# ATmega1284p_breakout.net
KiCad netlist of a schematic drawn in Altium Designer
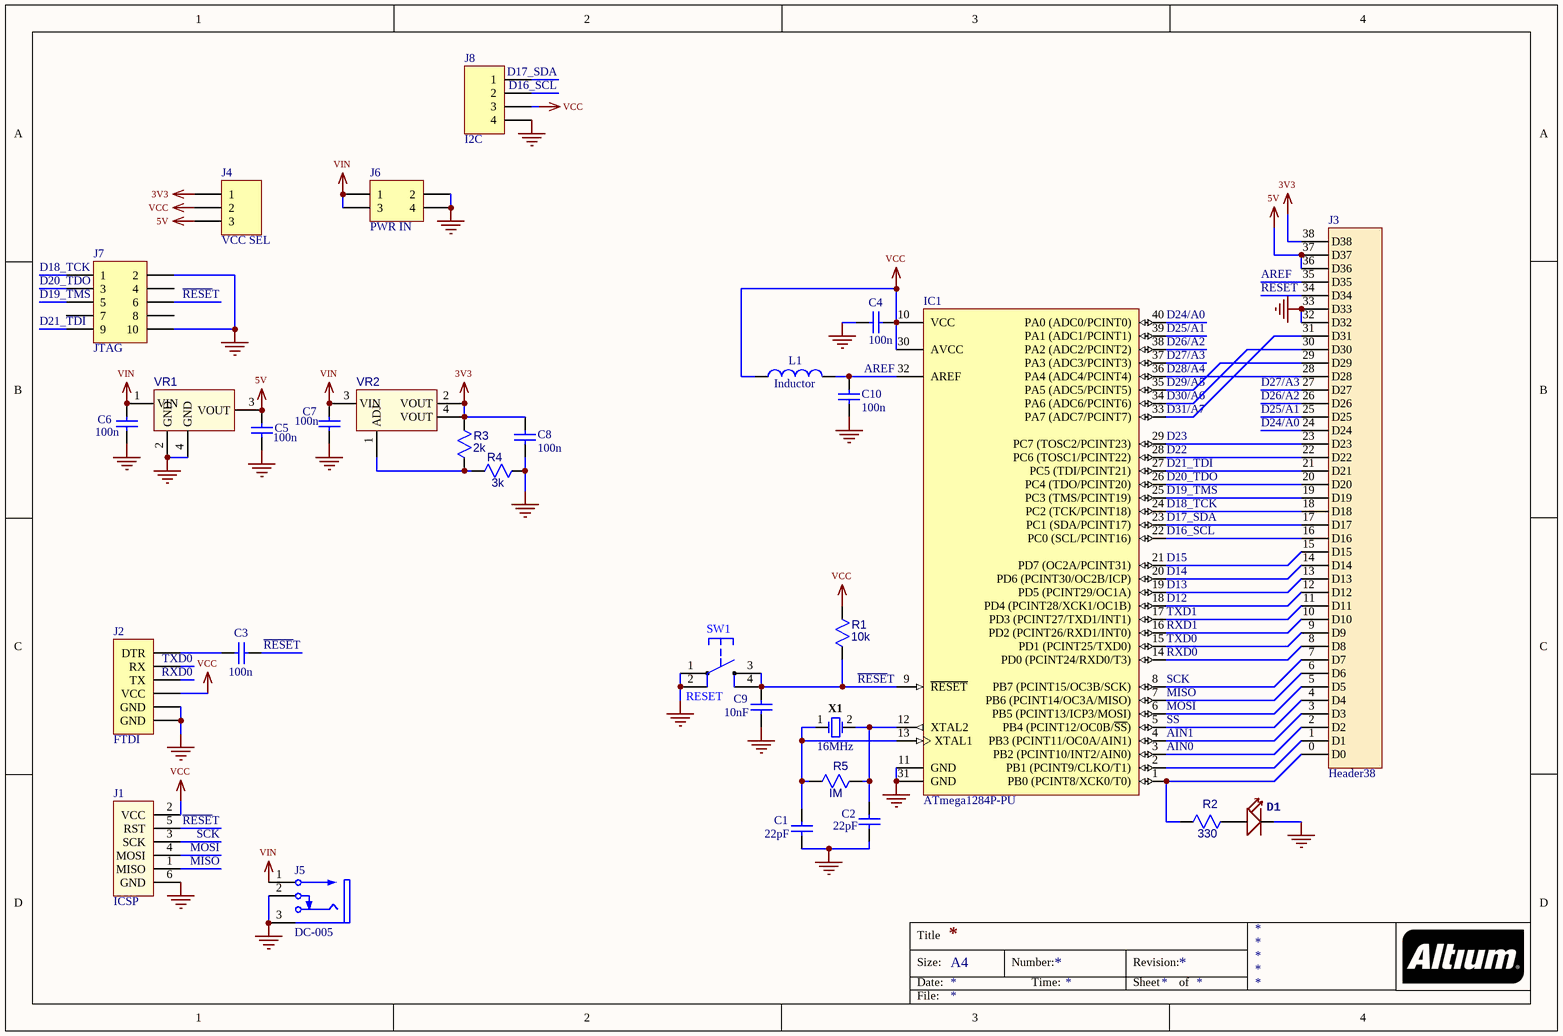
[diagram p0: ATmega1284p_breakout.SchDoc]

(export (version "E")
  (design (tool "Eeschema 10.0.6"))
  (components
    (comp (ref "C1")
      (value "22pF")
      (footprint "RESC0805(2012)_M:RESC0805(2012)_M")
      (description "Capacitor (Semiconductor SIM Model)")
      (fields (field (name "Comment") "Cap Semi"))
      (libsource (lib "Miscellaneous Devices") (part "Cap Semi"))
    )
    (comp (ref "C2")
      (value "22pF")
      (footprint "RESC0805(2012)_M:RESC0805(2012)_M")
      (description "Capacitor (Semiconductor SIM Model)")
      (fields (field (name "Comment") "Cap Semi"))
      (libsource (lib "Miscellaneous Devices") (part "Cap Semi"))
    )
    (comp (ref "C3")
      (value "100n")
      (footprint "RESC0805(2012)_M:RESC0805(2012)_M")
      (description "Capacitor (Semiconductor SIM Model)")
      (fields (field (name "Comment") "Cap Semi"))
      (libsource (lib "Miscellaneous Devices") (part "Cap Semi"))
    )
    (comp (ref "C4")
      (value "100n")
      (footprint "RESC0805(2012)_M:RESC0805(2012)_M")
      (description "Capacitor (Semiconductor SIM Model)")
      (fields (field (name "Comment") "Cap Semi"))
      (libsource (lib "Miscellaneous Devices") (part "Cap Semi"))
    )
    (comp (ref "C5")
      (value "100n")
      (footprint "RESC0805(2012)_M:RESC0805(2012)_M")
      (description "Capacitor (Semiconductor SIM Model)")
      (fields (field (name "Comment") "Cap Semi"))
      (libsource (lib "Miscellaneous Devices") (part "Cap Semi"))
    )
    (comp (ref "C6")
      (value "100n")
      (footprint "RESC0805(2012)_M:RESC0805(2012)_M")
      (description "Capacitor (Semiconductor SIM Model)")
      (fields (field (name "Comment") "Cap Semi"))
      (libsource (lib "Miscellaneous Devices") (part "Cap Semi"))
    )
    (comp (ref "C7")
      (value "100n")
      (footprint "RESC0805(2012)_M:RESC0805(2012)_M")
      (description "Capacitor (Semiconductor SIM Model)")
      (fields (field (name "Comment") "Cap Semi"))
      (libsource (lib "Miscellaneous Devices") (part "Cap Semi"))
    )
    (comp (ref "C8")
      (value "100n")
      (footprint "RESC0805(2012)_M:RESC0805(2012)_M")
      (description "Capacitor (Semiconductor SIM Model)")
      (fields (field (name "Comment") "Cap Semi"))
      (libsource (lib "Miscellaneous Devices") (part "Cap Semi"))
    )
    (comp (ref "C9")
      (value "10nF")
      (footprint "RESC0805(2012)_M:RESC0805(2012)_M")
      (description "Capacitor (Semiconductor SIM Model)")
      (fields (field (name "Comment") "Cap Semi"))
      (libsource (lib "Miscellaneous Devices") (part "Cap Semi"))
    )
    (comp (ref "C10")
      (value "100n")
      (footprint "RESC0805(2012)_M:RESC0805(2012)_M")
      (description "Capacitor (Semiconductor SIM Model)")
      (fields (field (name "Comment") "Cap Semi"))
      (libsource (lib "Miscellaneous Devices") (part "Cap Semi"))
    )
    (comp (ref "D1")
      (value "LED")
      (footprint "LED-0805")
      (fields (field (name "MPN") "17-215SURC/S530-A2/TR8"))
      (libsource (lib "105848_revD3") (part "SMD-LED-CLEAR-RED(0805)"))
    )
    (comp (ref "IC1")
      (value "ATmega1284P-PU")
      (footprint "40P6")
      (libsource (lib "Atmel Microcontroller megaAVR") (part "ATmega1284P-PU"))
    )
    (comp (ref "J1")
      (value "ICSP")
      (footprint "ICSP")
      (description "In-Circuit Serial Programming Header")
      (libsource (lib "AltiumIntegratedLibrary") (part "ICSP"))
    )
    (comp (ref "J2")
      (value "FTDI")
      (footprint "HDR1X6")
      (description "Header, 6-Pin")
      (fields (field (name "PUBLISHER") "Altium Limited"))
      (libsource (lib "Miscellaneous Connectors") (part "MHDR1X6"))
    )
    (comp (ref "J3")
      (value "Header38")
      (footprint "Header38")
      (libsource (lib "ATmega1284p_breakout") (part "Component_1"))
    )
    (comp (ref "J4")
      (value "VCC SEL")
      (footprint "HDR1X3")
      (description "Header, 3-Pin")
      (fields (field (name "PUBLISHER") "Altium Limited"))
      (libsource (lib "Miscellaneous Connectors") (part "Header 3"))
    )
    (comp (ref "J5")
      (value "DC-005")
      (footprint "DCJ3P-14.2X11.0X9.0MM")
      (libsource (lib "ATmega1284p_breakout") (part "DC BARREL"))
    )
    (comp (ref "J6")
      (value "PWR IN")
      (footprint "HDR2X2")
      (description "Header, 2-Pin, Dual row")
      (fields (field (name "PUBLISHER") "Altium Limited"))
      (libsource (lib "Miscellaneous Connectors") (part "Header 2X2"))
    )
    (comp (ref "J7")
      (value "JTAG")
      (footprint "HDR2X5")
      (description "Header, 5-Pin, Dual row")
      (fields (field (name "PUBLISHER") "Altium Limited"))
      (libsource (lib "Miscellaneous Connectors") (part "Header 5X2"))
    )
    (comp (ref "J8")
      (value "I2C")
      (footprint "HDR1X4")
      (description "Header, 4-Pin")
      (fields (field (name "PUBLISHER") "Altium Limited"))
      (libsource (lib "Miscellaneous Connectors") (part "Header 4"))
    )
    (comp (ref "L1")
      (value "Inductor")
      (footprint "2029")
      (fields (field (name "PUBLISHER") "Altium Limited"))
      (libsource (lib "Miscellaneous Devices") (part "Inductor"))
    )
    (comp (ref "R1")
      (value "10k")
      (footprint "CAPC0805(2012)75_N")
      (description "RES_0805")
      (libsource (lib "AltiumIntegratedLibrary") (part "RES_0805"))
    )
    (comp (ref "R2")
      (value "330")
      (footprint "CAPC0805(2012)75_N")
      (description "RES_0805")
      (libsource (lib "AltiumIntegratedLibrary") (part "RES_0805"))
    )
    (comp (ref "R3")
      (value "2k")
      (footprint "CAPC0805(2012)75_N")
      (description "RES_0805")
      (libsource (lib "AltiumIntegratedLibrary") (part "RES_0805"))
    )
    (comp (ref "R4")
      (value "3k")
      (footprint "CAPC0805(2012)75_N")
      (description "RES_0805")
      (libsource (lib "AltiumIntegratedLibrary") (part "RES_0805"))
    )
    (comp (ref "R5")
      (value "IM")
      (footprint "CAPC0805(2012)75_N")
      (description "RES_0805")
      (libsource (lib "AltiumIntegratedLibrary") (part "RES_0805"))
    )
    (comp (ref "SW1")
      (value "RESET")
      (footprint "TACT_SW")
      (libsource (lib "AltiumIntegratedLibrary") (part "TACT_SW"))
    )
    (comp (ref "VR1")
      (value "LDL1117S50R")
      (footprint "SOT223_M")
      (description "Fixed 5V Voltage Regulator")
      (fields (field (name "MFR") "TI") (field (name "MPN") "LM340MP-5.0"))
      (libsource (lib "105848_revD3") (part "LM317"))
    )
    (comp (ref "VR2")
      (value "LM117")
      (footprint "SOT223_M")
      (description "Adjustable Voltage Regulator")
      (fields (field (name "MFR") "TI") (field (name "MPN") "LM340MP-5.0"))
      (libsource (lib "") (part "LM317_1"))
    )
    (comp (ref "X1")
      (value "16MHz")
      (footprint "Crystal")
      (libsource (lib "ATmega1284p_breakout") (part "XTAL-HC"))
    )
  )
  (nets
    (net (code "1") (name "/AIN0") (class "Default")
      (node (ref "IC1") (pin "3") (pinfunction "PB2_(PCINT10/INT2/AIN0)_3") (pintype "bidirectional"))
      (node (ref "J3") (pin "2") (pinfunction "D2_2") (pintype "passive"))
    )
    (net (code "2") (name "/AIN1") (class "Default")
      (node (ref "IC1") (pin "4") (pinfunction "PB3_(PCINT11/OC0A/AIN1)_4") (pintype "bidirectional"))
      (node (ref "J3") (pin "3") (pinfunction "D3_3") (pintype "passive"))
    )
    (net (code "3") (name "/AREF") (class "Default")
      (node (ref "C10") (pin "2") (pinfunction "2_2") (pintype "passive"))
      (node (ref "IC1") (pin "32") (pinfunction "AREF_32") (pintype "power_in"))
      (node (ref "J3") (pin "35") (pinfunction "D35_35") (pintype "passive"))
      (node (ref "L1") (pin "2") (pinfunction "2_2") (pintype "passive"))
    )
    (net (code "4") (name "/D12") (class "Default")
      (node (ref "IC1") (pin "18") (pinfunction "PD4_(PCINT28/XCK1/OC1B)_18") (pintype "bidirectional"))
      (node (ref "J3") (pin "12") (pinfunction "D12_12") (pintype "passive"))
    )
    (net (code "5") (name "/D13") (class "Default")
      (node (ref "IC1") (pin "19") (pinfunction "PD5_(PCINT29/OC1A)_19") (pintype "bidirectional"))
      (node (ref "J3") (pin "13") (pinfunction "D13_13") (pintype "passive"))
    )
    (net (code "6") (name "/D14") (class "Default")
      (node (ref "IC1") (pin "20") (pinfunction "PD6_(PCINT30/OC2B/ICP)_20") (pintype "bidirectional"))
      (node (ref "J3") (pin "14") (pinfunction "D14_14") (pintype "passive"))
    )
    (net (code "7") (name "/D15") (class "Default")
      (node (ref "IC1") (pin "21") (pinfunction "PD7_(OC2A/PCINT31)_21") (pintype "bidirectional"))
      (node (ref "J3") (pin "15") (pinfunction "D15_15") (pintype "passive"))
    )
    (net (code "8") (name "/D16_SCL") (class "Default")
      (node (ref "IC1") (pin "22") (pinfunction "PC0_(SCL/PCINT16)_22") (pintype "bidirectional"))
      (node (ref "J3") (pin "16") (pinfunction "D16_16") (pintype "passive"))
      (node (ref "J8") (pin "2") (pinfunction "2_2") (pintype "passive"))
    )
    (net (code "9") (name "/D17_SDA") (class "Default")
      (node (ref "IC1") (pin "23") (pinfunction "PC1_(SDA/PCINT17)_23") (pintype "bidirectional"))
      (node (ref "J3") (pin "17") (pinfunction "D17_17") (pintype "passive"))
      (node (ref "J8") (pin "1") (pinfunction "1_1") (pintype "passive"))
    )
    (net (code "10") (name "/D18_TCK") (class "Default")
      (node (ref "IC1") (pin "24") (pinfunction "PC2_(TCK/PCINT18)_24") (pintype "bidirectional"))
      (node (ref "J3") (pin "18") (pinfunction "D18_18") (pintype "passive"))
      (node (ref "J7") (pin "1") (pinfunction "1_1") (pintype "passive"))
    )
    (net (code "11") (name "/D19_TMS") (class "Default")
      (node (ref "IC1") (pin "25") (pinfunction "PC3_(TMS/PCINT19)_25") (pintype "bidirectional"))
      (node (ref "J3") (pin "19") (pinfunction "D19_19") (pintype "passive"))
      (node (ref "J7") (pin "5") (pinfunction "5_5") (pintype "passive"))
    )
    (net (code "12") (name "/D20_TDO") (class "Default")
      (node (ref "IC1") (pin "26") (pinfunction "PC4_(TDO/PCINT20)_26") (pintype "bidirectional"))
      (node (ref "J3") (pin "20") (pinfunction "D20_20") (pintype "passive"))
      (node (ref "J7") (pin "3") (pinfunction "3_3") (pintype "passive"))
    )
    (net (code "13") (name "/D21_TDI") (class "Default")
      (node (ref "IC1") (pin "27") (pinfunction "PC5_(TDI/PCINT21)_27") (pintype "bidirectional"))
      (node (ref "J3") (pin "21") (pinfunction "D21_21") (pintype "passive"))
      (node (ref "J7") (pin "9") (pinfunction "9_9") (pintype "passive"))
    )
    (net (code "14") (name "/D22") (class "Default")
      (node (ref "IC1") (pin "28") (pinfunction "PC6_(TOSC1/PCINT22)_28") (pintype "bidirectional"))
      (node (ref "J3") (pin "22") (pinfunction "D22_22") (pintype "passive"))
    )
    (net (code "15") (name "/D23") (class "Default")
      (node (ref "IC1") (pin "29") (pinfunction "PC7_(TOSC2/PCINT23)_29") (pintype "bidirectional"))
      (node (ref "J3") (pin "23") (pinfunction "D23_23") (pintype "passive"))
    )
    (net (code "16") (name "/D24{slash}A0") (class "Default")
      (node (ref "IC1") (pin "40") (pinfunction "PA0_(ADC0/PCINT0)_40") (pintype "bidirectional"))
      (node (ref "J3") (pin "24") (pinfunction "D24_24") (pintype "passive"))
    )
    (net (code "17") (name "/D25{slash}A1") (class "Default")
      (node (ref "IC1") (pin "39") (pinfunction "PA1_(ADC1/PCINT1)_39") (pintype "bidirectional"))
      (node (ref "J3") (pin "25") (pinfunction "D25_25") (pintype "passive"))
    )
    (net (code "18") (name "/D26{slash}A2") (class "Default")
      (node (ref "IC1") (pin "38") (pinfunction "PA2_(ADC2/PCINT2)_38") (pintype "bidirectional"))
      (node (ref "J3") (pin "26") (pinfunction "D26_26") (pintype "passive"))
    )
    (net (code "19") (name "/D27{slash}A3") (class "Default")
      (node (ref "IC1") (pin "37") (pinfunction "PA3_(ADC3/PCINT3)_37") (pintype "bidirectional"))
      (node (ref "J3") (pin "27") (pinfunction "D27_27") (pintype "passive"))
    )
    (net (code "20") (name "/D28{slash}A4") (class "Default")
      (node (ref "IC1") (pin "36") (pinfunction "PA4_(ADC4/PCINT4)_36") (pintype "bidirectional"))
      (node (ref "J3") (pin "28") (pinfunction "D28_28") (pintype "passive"))
    )
    (net (code "21") (name "/D29{slash}A5") (class "Default")
      (node (ref "IC1") (pin "35") (pinfunction "PA5_(ADC5/PCINT5)_35") (pintype "bidirectional"))
      (node (ref "J3") (pin "29") (pinfunction "D29_29") (pintype "passive"))
    )
    (net (code "22") (name "/D30{slash}A6") (class "Default")
      (node (ref "IC1") (pin "34") (pinfunction "PA6_(ADC6/PCINT6)_34") (pintype "bidirectional"))
      (node (ref "J3") (pin "30") (pinfunction "D30_30") (pintype "passive"))
    )
    (net (code "23") (name "/D31{slash}A7") (class "Default")
      (node (ref "IC1") (pin "33") (pinfunction "PA7_(ADC7/PCINT7)_33") (pintype "bidirectional"))
      (node (ref "J3") (pin "31") (pinfunction "D31_31") (pintype "passive"))
    )
    (net (code "24") (name "/MISO") (class "Default")
      (node (ref "IC1") (pin "7") (pinfunction "PB6_(PCINT14/OC3A/MISO)_7") (pintype "bidirectional"))
      (node (ref "J1") (pin "1") (pinfunction "MISO_1") (pintype "passive"))
      (node (ref "J3") (pin "6") (pinfunction "D6_6") (pintype "passive"))
    )
    (net (code "25") (name "/MOSI") (class "Default")
      (node (ref "IC1") (pin "6") (pinfunction "PB5_(PCINT13/ICP3/MOSI)_6") (pintype "bidirectional"))
      (node (ref "J1") (pin "4") (pinfunction "MOSI_4") (pintype "passive"))
      (node (ref "J3") (pin "5") (pinfunction "D5_5") (pintype "passive"))
    )
    (net (code "26") (name "/RXD0") (class "Default")
      (node (ref "IC1") (pin "14") (pinfunction "PD0_(PCINT24/RXD0/T3)_14") (pintype "bidirectional"))
      (node (ref "J2") (pin "3") (pinfunction "TX_3") (pintype "passive"))
      (node (ref "J3") (pin "8") (pinfunction "D8_8") (pintype "passive"))
    )
    (net (code "27") (name "/RXD1") (class "Default")
      (node (ref "IC1") (pin "16") (pinfunction "PD2_(PCINT26/RXD1/INT0)_16") (pintype "bidirectional"))
      (node (ref "J3") (pin "10") (pinfunction "D10_10") (pintype "passive"))
    )
    (net (code "28") (name "/SCK") (class "Default")
      (node (ref "IC1") (pin "8") (pinfunction "PB7_(PCINT15/OC3B/SCK)_8") (pintype "bidirectional"))
      (node (ref "J1") (pin "3") (pinfunction "SCK_3") (pintype "passive"))
      (node (ref "J3") (pin "7") (pinfunction "D7_7") (pintype "passive"))
    )
    (net (code "29") (name "/TXD0") (class "Default")
      (node (ref "IC1") (pin "15") (pinfunction "PD1_(PCINT25/TXD0)_15") (pintype "bidirectional"))
      (node (ref "J2") (pin "2") (pinfunction "RX_2") (pintype "passive"))
      (node (ref "J3") (pin "9") (pinfunction "D9_9") (pintype "passive"))
    )
    (net (code "30") (name "/TXD1") (class "Default")
      (node (ref "IC1") (pin "17") (pinfunction "PD3_(PCINT27/TXD1/INT1)_17") (pintype "bidirectional"))
      (node (ref "J3") (pin "11") (pinfunction "D11_11") (pintype "passive"))
    )
    (net (code "31") (name "/~{RESE}T") (class "Default")
      (node (ref "C3") (pin "2") (pinfunction "2_2") (pintype "passive"))
      (node (ref "C9") (pin "2") (pinfunction "2_2") (pintype "passive"))
      (node (ref "IC1") (pin "9") (pinfunction "~{RESET}_9") (pintype "input"))
      (node (ref "J1") (pin "5") (pinfunction "RST_5") (pintype "passive"))
      (node (ref "J3") (pin "34") (pinfunction "D34_34") (pintype "passive"))
      (node (ref "J7") (pin "6") (pinfunction "6_6") (pintype "passive"))
      (node (ref "R1") (pin "1") (pintype "passive"))
      (node (ref "SW1") (pin "3") (pinfunction "3_3") (pintype "passive"))
      (node (ref "SW1") (pin "4") (pinfunction "4_4") (pintype "passive"))
    )
    (net (code "32") (name "/~{S}S") (class "Default")
      (node (ref "IC1") (pin "5") (pinfunction "PB4_(PCINT12/OC0B/~{SS})_5") (pintype "bidirectional"))
      (node (ref "J3") (pin "4") (pinfunction "D4_4") (pintype "passive"))
    )
    (net (code "33") (name "3V3") (class "Default")
      (node (ref "C8") (pin "2") (pinfunction "2_2") (pintype "passive"))
      (node (ref "J3") (pin "38") (pinfunction "D38_38") (pintype "passive"))
      (node (ref "J4") (pin "1") (pinfunction "1_1") (pintype "passive"))
      (node (ref "R3") (pin "2") (pintype "passive"))
      (node (ref "VR2") (pin "2") (pinfunction "VOUT_2") (pintype "passive"))
      (node (ref "VR2") (pin "4") (pinfunction "VOUT_4") (pintype "passive"))
    )
    (net (code "34") (name "5V") (class "Default")
      (node (ref "C5") (pin "2") (pinfunction "2_2") (pintype "passive"))
      (node (ref "J3") (pin "36") (pinfunction "D36_36") (pintype "passive"))
      (node (ref "J3") (pin "37") (pinfunction "D37_37") (pintype "passive"))
      (node (ref "J4") (pin "3") (pinfunction "3_3") (pintype "passive"))
      (node (ref "VR1") (pin "3") (pinfunction "VOUT_3") (pintype "passive"))
    )
    (net (code "35") (name "GND") (class "Default")
      (node (ref "C1") (pin "1") (pinfunction "1_1") (pintype "passive"))
      (node (ref "C10") (pin "1") (pinfunction "1_1") (pintype "passive"))
      (node (ref "C2") (pin "1") (pinfunction "1_1") (pintype "passive"))
      (node (ref "C4") (pin "1") (pinfunction "1_1") (pintype "passive"))
      (node (ref "C5") (pin "1") (pinfunction "1_1") (pintype "passive"))
      (node (ref "C6") (pin "1") (pinfunction "1_1") (pintype "passive"))
      (node (ref "C7") (pin "1") (pinfunction "1_1") (pintype "passive"))
      (node (ref "C8") (pin "1") (pinfunction "1_1") (pintype "passive"))
      (node (ref "C9") (pin "1") (pinfunction "1_1") (pintype "passive"))
      (node (ref "D1") (pin "-") (pinfunction "-_-") (pintype "passive"))
      (node (ref "IC1") (pin "11") (pinfunction "GND_11") (pintype "power_in"))
      (node (ref "IC1") (pin "31") (pinfunction "GND_31") (pintype "power_in"))
      (node (ref "J1") (pin "6") (pinfunction "GND_6") (pintype "passive"))
      (node (ref "J2") (pin "5") (pinfunction "GND_5") (pintype "passive"))
      (node (ref "J2") (pin "6") (pinfunction "GND_6") (pintype "passive"))
      (node (ref "J3") (pin "32") (pinfunction "D32_32") (pintype "passive"))
      (node (ref "J3") (pin "33") (pinfunction "D33_33") (pintype "passive"))
      (node (ref "J5") (pin "2") (pinfunction "2_2") (pintype "passive"))
      (node (ref "J5") (pin "3") (pinfunction "3_3") (pintype "passive"))
      (node (ref "J6") (pin "2") (pinfunction "2_2") (pintype "passive"))
      (node (ref "J6") (pin "4") (pinfunction "4_4") (pintype "passive"))
      (node (ref "J7") (pin "10") (pinfunction "10_10") (pintype "passive"))
      (node (ref "J7") (pin "2") (pinfunction "2_2") (pintype "passive"))
      (node (ref "J8") (pin "4") (pinfunction "4_4") (pintype "passive"))
      (node (ref "R4") (pin "1") (pintype "passive"))
      (node (ref "SW1") (pin "1") (pinfunction "1_1") (pintype "passive"))
      (node (ref "SW1") (pin "2") (pinfunction "2_2") (pintype "passive"))
      (node (ref "VR1") (pin "2") (pinfunction "GND_2") (pintype "power_in"))
      (node (ref "VR1") (pin "4") (pinfunction "GND_4") (pintype "passive"))
    )
    (net (code "36") (name "Net-(D1-Pad+)") (class "Default")
      (node (ref "D1") (pin "+") (pinfunction "+_+") (pintype "passive"))
      (node (ref "R2") (pin "1") (pintype "passive"))
    )
    (net (code "37") (name "Net-(IC1-PB0_(PCINT8{slash}XCK0{slash}T0))") (class "Default")
      (node (ref "IC1") (pin "1") (pinfunction "PB0_(PCINT8/XCK0/T0)_1") (pintype "bidirectional"))
      (node (ref "J3") (pin "0") (pinfunction "D0_0") (pintype "passive"))
      (node (ref "R2") (pin "2") (pintype "passive"))
    )
    (net (code "38") (name "Net-(IC1-PB1_(PCINT9{slash}CLKO{slash}T1))") (class "Default")
      (node (ref "IC1") (pin "2") (pinfunction "PB1_(PCINT9/CLKO/T1)_2") (pintype "bidirectional"))
      (node (ref "J3") (pin "1") (pinfunction "D1_1") (pintype "passive"))
    )
    (net (code "39") (name "Net-(IC1-XTAL1)") (class "Default")
      (node (ref "C1") (pin "2") (pinfunction "2_2") (pintype "passive"))
      (node (ref "IC1") (pin "13") (pinfunction "XTAL1_13") (pintype "input"))
      (node (ref "R5") (pin "2") (pintype "passive"))
      (node (ref "X1") (pin "1") (pinfunction "1_1") (pintype "passive"))
    )
    (net (code "40") (name "Net-(IC1-XTAL2)") (class "Default")
      (node (ref "C2") (pin "2") (pinfunction "2_2") (pintype "passive"))
      (node (ref "IC1") (pin "12") (pinfunction "XTAL2_12") (pintype "output"))
      (node (ref "R5") (pin "1") (pintype "passive"))
      (node (ref "X1") (pin "2") (pinfunction "2_2") (pintype "passive"))
    )
    (net (code "41") (name "Net-(J2-DTR)") (class "Default")
      (node (ref "C3") (pin "1") (pinfunction "1_1") (pintype "passive"))
      (node (ref "J2") (pin "1") (pinfunction "DTR_1") (pintype "passive"))
    )
    (net (code "42") (name "Net-(VR2-ADJ)") (class "Default")
      (node (ref "R3") (pin "1") (pintype "passive"))
      (node (ref "R4") (pin "2") (pintype "passive"))
      (node (ref "VR2") (pin "1") (pinfunction "ADJ_1") (pintype "passive"))
    )
    (net (code "43") (name "VCC") (class "Default")
      (node (ref "C4") (pin "2") (pinfunction "2_2") (pintype "passive"))
      (node (ref "IC1") (pin "10") (pinfunction "VCC_10") (pintype "power_in"))
      (node (ref "IC1") (pin "30") (pinfunction "AVCC_30") (pintype "power_in"))
      (node (ref "J1") (pin "2") (pinfunction "VCC_2") (pintype "passive"))
      (node (ref "J2") (pin "4") (pinfunction "VCC_4") (pintype "passive"))
      (node (ref "J4") (pin "2") (pinfunction "2_2") (pintype "passive"))
      (node (ref "J8") (pin "3") (pinfunction "3_3") (pintype "passive"))
      (node (ref "L1") (pin "1") (pinfunction "1_1") (pintype "passive"))
      (node (ref "R1") (pin "2") (pintype "passive"))
    )
    (net (code "44") (name "VIN") (class "Default")
      (node (ref "C6") (pin "2") (pinfunction "2_2") (pintype "passive"))
      (node (ref "C7") (pin "2") (pinfunction "2_2") (pintype "passive"))
      (node (ref "J5") (pin "1") (pinfunction "1_1") (pintype "passive"))
      (node (ref "J6") (pin "1") (pinfunction "1_1") (pintype "passive"))
      (node (ref "J6") (pin "3") (pinfunction "3_3") (pintype "passive"))
      (node (ref "VR1") (pin "1") (pinfunction "VIN_1") (pintype "passive"))
      (node (ref "VR2") (pin "3") (pinfunction "VIN_3") (pintype "passive"))
    )
    (net (code "45") (name "unconnected-(J7-Pad4)") (class "Default")
      (node (ref "J7") (pin "4") (pinfunction "4_4") (pintype "passive"))
    )
    (net (code "46") (name "unconnected-(J7-Pad7)") (class "Default")
      (node (ref "J7") (pin "7") (pinfunction "7_7") (pintype "passive"))
    )
    (net (code "47") (name "unconnected-(J7-Pad8)") (class "Default")
      (node (ref "J7") (pin "8") (pinfunction "8_8") (pintype "passive"))
    )
  )
)
